# domino4_EPB.net
KiCad netlist of a schematic drawn in EAGLE
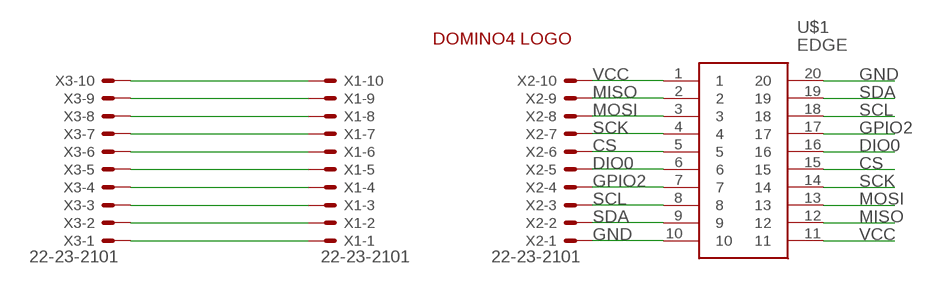
[diagram p0: schematic, sheet 1]

(export (version "E")
  (design (tool "Eeschema 10.0.6"))
  (components
    (comp (ref "U$1")
      (value "EDGE")
      (footprint "eagle-import:EDGE")
      (libsource (lib "eagle-import") (part "EDGE"))
    )
    (comp (ref "U$2")
      (value "DOMINO4_LOGO")
      (footprint "eagle-import:DOMINO4_LOGO")
      (libsource (lib "eagle-import") (part "DOMINO4_LOGO"))
    )
    (comp (ref "X1")
      (value "22-23-2101")
      (footprint "eagle-import:22-23-2101")
      (fields (field (name "MF") "MOLEX"))
      (libsource (lib "eagle-import") (part "22-23-2101"))
    )
    (comp (ref "X2")
      (value "22-23-2101")
      (footprint "eagle-import:22-23-2101")
      (fields (field (name "MF") "MOLEX"))
      (libsource (lib "eagle-import") (part "22-23-2101"))
    )
    (comp (ref "X3")
      (value "22-23-2101")
      (footprint "eagle-import:22-23-2101")
      (fields (field (name "MF") "MOLEX"))
      (libsource (lib "eagle-import") (part "22-23-2101"))
    )
  )
  (nets
    (net (code "1") (name "/CS") (class "Default")
      (node (ref "U$1") (pin "15") (pinfunction "15_15") (pintype "bidirectional"))
      (node (ref "U$1") (pin "5") (pinfunction "5_5") (pintype "bidirectional"))
      (node (ref "X2") (pin "6") (pinfunction "S_6") (pintype "passive"))
    )
    (net (code "2") (name "/DIO0") (class "Default")
      (node (ref "U$1") (pin "16") (pinfunction "16_16") (pintype "bidirectional"))
      (node (ref "U$1") (pin "6") (pinfunction "6_6") (pintype "bidirectional"))
      (node (ref "X2") (pin "5") (pinfunction "S_5") (pintype "passive"))
    )
    (net (code "3") (name "/GND") (class "Default")
      (node (ref "U$1") (pin "10") (pinfunction "10_10") (pintype "bidirectional"))
      (node (ref "U$1") (pin "20") (pinfunction "20_20") (pintype "bidirectional"))
      (node (ref "X2") (pin "1") (pinfunction "S_1") (pintype "passive"))
    )
    (net (code "4") (name "/GPIO2") (class "Default")
      (node (ref "U$1") (pin "17") (pinfunction "17_17") (pintype "bidirectional"))
      (node (ref "U$1") (pin "7") (pinfunction "7_7") (pintype "bidirectional"))
      (node (ref "X2") (pin "4") (pinfunction "S_4") (pintype "passive"))
    )
    (net (code "5") (name "/MISO") (class "Default")
      (node (ref "U$1") (pin "12") (pinfunction "12_12") (pintype "bidirectional"))
      (node (ref "U$1") (pin "2") (pinfunction "2_2") (pintype "bidirectional"))
      (node (ref "X2") (pin "9") (pinfunction "S_9") (pintype "passive"))
    )
    (net (code "6") (name "/MOSI") (class "Default")
      (node (ref "U$1") (pin "13") (pinfunction "13_13") (pintype "bidirectional"))
      (node (ref "U$1") (pin "3") (pinfunction "3_3") (pintype "bidirectional"))
      (node (ref "X2") (pin "8") (pinfunction "S_8") (pintype "passive"))
    )
    (net (code "7") (name "/SCK") (class "Default")
      (node (ref "U$1") (pin "14") (pinfunction "14_14") (pintype "bidirectional"))
      (node (ref "U$1") (pin "4") (pinfunction "4_4") (pintype "bidirectional"))
      (node (ref "X2") (pin "7") (pinfunction "S_7") (pintype "passive"))
    )
    (net (code "8") (name "/SCL") (class "Default")
      (node (ref "U$1") (pin "18") (pinfunction "18_18") (pintype "bidirectional"))
      (node (ref "U$1") (pin "8") (pinfunction "8_8") (pintype "bidirectional"))
      (node (ref "X2") (pin "3") (pinfunction "S_3") (pintype "passive"))
    )
    (net (code "9") (name "/SDA") (class "Default")
      (node (ref "U$1") (pin "19") (pinfunction "19_19") (pintype "bidirectional"))
      (node (ref "U$1") (pin "9") (pinfunction "9_9") (pintype "bidirectional"))
      (node (ref "X2") (pin "2") (pinfunction "S_2") (pintype "passive"))
    )
    (net (code "10") (name "/VCC") (class "Default")
      (node (ref "U$1") (pin "1") (pinfunction "1_1") (pintype "bidirectional"))
      (node (ref "U$1") (pin "11") (pinfunction "11_11") (pintype "bidirectional"))
      (node (ref "X2") (pin "10") (pinfunction "S_10") (pintype "passive"))
    )
    (net (code "11") (name "Net-(X1A-S)") (class "Default")
      (node (ref "X1") (pin "1") (pinfunction "S_1") (pintype "passive"))
      (node (ref "X3") (pin "1") (pinfunction "S_1") (pintype "passive"))
    )
    (net (code "12") (name "Net-(X1B-S)") (class "Default")
      (node (ref "X1") (pin "10") (pinfunction "S_10") (pintype "passive"))
      (node (ref "X3") (pin "10") (pinfunction "S_10") (pintype "passive"))
    )
    (net (code "13") (name "Net-(X1C-S)") (class "Default")
      (node (ref "X1") (pin "2") (pinfunction "S_2") (pintype "passive"))
      (node (ref "X3") (pin "2") (pinfunction "S_2") (pintype "passive"))
    )
    (net (code "14") (name "Net-(X1D-S)") (class "Default")
      (node (ref "X1") (pin "3") (pinfunction "S_3") (pintype "passive"))
      (node (ref "X3") (pin "3") (pinfunction "S_3") (pintype "passive"))
    )
    (net (code "15") (name "Net-(X1E-S)") (class "Default")
      (node (ref "X1") (pin "4") (pinfunction "S_4") (pintype "passive"))
      (node (ref "X3") (pin "4") (pinfunction "S_4") (pintype "passive"))
    )
    (net (code "16") (name "Net-(X1F-S)") (class "Default")
      (node (ref "X1") (pin "5") (pinfunction "S_5") (pintype "passive"))
      (node (ref "X3") (pin "5") (pinfunction "S_5") (pintype "passive"))
    )
    (net (code "17") (name "Net-(X1G-S)") (class "Default")
      (node (ref "X1") (pin "6") (pinfunction "S_6") (pintype "passive"))
      (node (ref "X3") (pin "6") (pinfunction "S_6") (pintype "passive"))
    )
    (net (code "18") (name "Net-(X1H-S)") (class "Default")
      (node (ref "X1") (pin "7") (pinfunction "S_7") (pintype "passive"))
      (node (ref "X3") (pin "7") (pinfunction "S_7") (pintype "passive"))
    )
    (net (code "19") (name "Net-(X1I-S)") (class "Default")
      (node (ref "X1") (pin "8") (pinfunction "S_8") (pintype "passive"))
      (node (ref "X3") (pin "8") (pinfunction "S_8") (pintype "passive"))
    )
    (net (code "20") (name "Net-(X1J-S)") (class "Default")
      (node (ref "X1") (pin "9") (pinfunction "S_9") (pintype "passive"))
      (node (ref "X3") (pin "9") (pinfunction "S_9") (pintype "passive"))
    )
  )
)
